# APM9328_CONNECTORL.net
KiCad netlist of a schematic drawn in Altium Designer
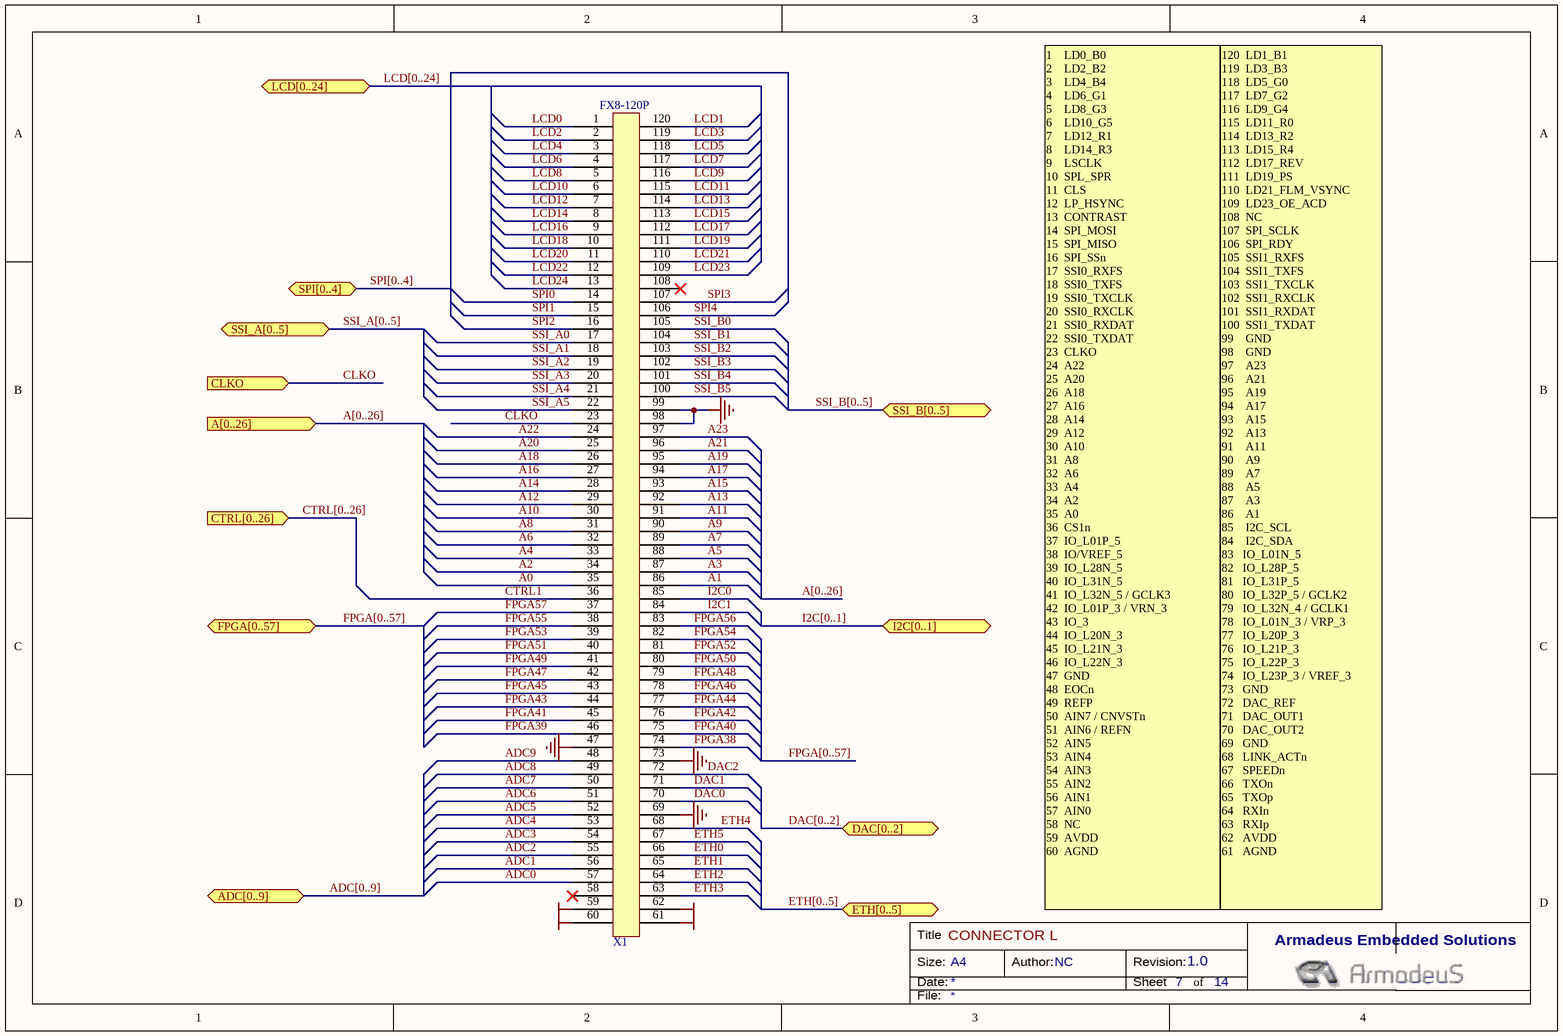
[diagram p0: APM9328_CONNECTORL.SchDoc]

(export (version "E")
  (design (tool "Eeschema 10.0.6"))
  (components
    (comp (ref "X1")
      (value "FX8-120P")
      (footprint "FX8-120P")
      (description "Fine Pitch Connector")
      (fields (field (name "MANUFACTURER") "Hirose") (field (name "PART NUMBER") "FX8-120P-SV"))
      (libsource (lib "*") (part "FX8-120P"))
    )
  )
  (nets
    (net (code "68") (name "/A0") (class "Default") (node (ref "X1") (pin "35") (pintype "passive")))
    (net (code "69") (name "/A1") (class "Default") (node (ref "X1") (pin "86") (pintype "passive")))
    (net (code "70") (name "/A2") (class "Default") (node (ref "X1") (pin "34") (pintype "passive")))
    (net (code "71") (name "/A3") (class "Default") (node (ref "X1") (pin "87") (pintype "passive")))
    (net (code "72") (name "/A4") (class "Default") (node (ref "X1") (pin "33") (pintype "passive")))
    (net (code "73") (name "/A5") (class "Default") (node (ref "X1") (pin "88") (pintype "passive")))
    (net (code "74") (name "/A6") (class "Default") (node (ref "X1") (pin "32") (pintype "passive")))
    (net (code "75") (name "/A7") (class "Default") (node (ref "X1") (pin "89") (pintype "passive")))
    (net (code "76") (name "/A8") (class "Default") (node (ref "X1") (pin "31") (pintype "passive")))
    (net (code "77") (name "/A9") (class "Default") (node (ref "X1") (pin "90") (pintype "passive")))
    (net (code "78") (name "/A10") (class "Default") (node (ref "X1") (pin "30") (pintype "passive")))
    (net (code "79") (name "/A11") (class "Default") (node (ref "X1") (pin "91") (pintype "passive")))
    (net (code "80") (name "/A12") (class "Default") (node (ref "X1") (pin "29") (pintype "passive")))
    (net (code "81") (name "/A13") (class "Default") (node (ref "X1") (pin "92") (pintype "passive")))
    (net (code "82") (name "/A14") (class "Default") (node (ref "X1") (pin "28") (pintype "passive")))
    (net (code "83") (name "/A15") (class "Default") (node (ref "X1") (pin "93") (pintype "passive")))
    (net (code "84") (name "/A16") (class "Default") (node (ref "X1") (pin "27") (pintype "passive")))
    (net (code "85") (name "/A17") (class "Default") (node (ref "X1") (pin "94") (pintype "passive")))
    (net (code "86") (name "/A18") (class "Default") (node (ref "X1") (pin "26") (pintype "passive")))
    (net (code "87") (name "/A19") (class "Default") (node (ref "X1") (pin "95") (pintype "passive")))
    (net (code "88") (name "/A20") (class "Default") (node (ref "X1") (pin "25") (pintype "passive")))
    (net (code "89") (name "/A21") (class "Default") (node (ref "X1") (pin "96") (pintype "passive")))
    (net (code "90") (name "/A22") (class "Default") (node (ref "X1") (pin "24") (pintype "passive")))
    (net (code "91") (name "/A23") (class "Default") (node (ref "X1") (pin "97") (pintype "passive")))
    (net (code "92") (name "/ADC0") (class "Default") (node (ref "X1") (pin "57") (pintype "passive")))
    (net (code "93") (name "/ADC1") (class "Default") (node (ref "X1") (pin "56") (pintype "passive")))
    (net (code "94") (name "/ADC2") (class "Default") (node (ref "X1") (pin "55") (pintype "passive")))
    (net (code "95") (name "/ADC3") (class "Default") (node (ref "X1") (pin "54") (pintype "passive")))
    (net (code "96") (name "/ADC4") (class "Default") (node (ref "X1") (pin "53") (pintype "passive")))
    (net (code "97") (name "/ADC5") (class "Default") (node (ref "X1") (pin "52") (pintype "passive")))
    (net (code "98") (name "/ADC6") (class "Default") (node (ref "X1") (pin "51") (pintype "passive")))
    (net (code "99") (name "/ADC7") (class "Default") (node (ref "X1") (pin "50") (pintype "passive")))
    (net (code "100") (name "/ADC8") (class "Default") (node (ref "X1") (pin "49") (pintype "passive")))
    (net (code "101") (name "/ADC9") (class "Default") (node (ref "X1") (pin "48") (pintype "passive")))
    (net (code "104") (name "/CLKO") (class "Default") (node (ref "X1") (pin "23") (pintype "passive")))
    (net (code "105") (name "/CTRL1") (class "Default") (node (ref "X1") (pin "36") (pintype "passive")))
    (net (code "107") (name "/DAC0") (class "Default") (node (ref "X1") (pin "70") (pintype "passive")))
    (net (code "108") (name "/DAC1") (class "Default") (node (ref "X1") (pin "71") (pintype "passive")))
    (net (code "109") (name "/DAC2") (class "Default") (node (ref "X1") (pin "72") (pintype "passive")))
    (net (code "111") (name "/ETH0") (class "Default") (node (ref "X1") (pin "66") (pintype "passive")))
    (net (code "112") (name "/ETH1") (class "Default") (node (ref "X1") (pin "65") (pintype "passive")))
    (net (code "113") (name "/ETH2") (class "Default") (node (ref "X1") (pin "64") (pintype "passive")))
    (net (code "114") (name "/ETH3") (class "Default") (node (ref "X1") (pin "63") (pintype "passive")))
    (net (code "115") (name "/ETH4") (class "Default") (node (ref "X1") (pin "68") (pintype "passive")))
    (net (code "116") (name "/ETH5") (class "Default") (node (ref "X1") (pin "67") (pintype "passive")))
    (net (code "118") (name "/FPGA38") (class "Default") (node (ref "X1") (pin "74") (pintype "passive")))
    (net (code "119") (name "/FPGA39") (class "Default") (node (ref "X1") (pin "46") (pintype "passive")))
    (net (code "120") (name "/FPGA40") (class "Default") (node (ref "X1") (pin "75") (pintype "passive")))
    (net (code "121") (name "/FPGA41") (class "Default") (node (ref "X1") (pin "45") (pintype "passive")))
    (net (code "122") (name "/FPGA42") (class "Default") (node (ref "X1") (pin "76") (pintype "passive")))
    (net (code "123") (name "/FPGA43") (class "Default") (node (ref "X1") (pin "44") (pintype "passive")))
    (net (code "124") (name "/FPGA44") (class "Default") (node (ref "X1") (pin "77") (pintype "passive")))
    (net (code "125") (name "/FPGA45") (class "Default") (node (ref "X1") (pin "43") (pintype "passive")))
    (net (code "126") (name "/FPGA46") (class "Default") (node (ref "X1") (pin "78") (pintype "passive")))
    (net (code "127") (name "/FPGA47") (class "Default") (node (ref "X1") (pin "42") (pintype "passive")))
    (net (code "128") (name "/FPGA48") (class "Default") (node (ref "X1") (pin "79") (pintype "passive")))
    (net (code "129") (name "/FPGA49") (class "Default") (node (ref "X1") (pin "41") (pintype "passive")))
    (net (code "130") (name "/FPGA50") (class "Default") (node (ref "X1") (pin "80") (pintype "passive")))
    (net (code "131") (name "/FPGA51") (class "Default") (node (ref "X1") (pin "40") (pintype "passive")))
    (net (code "132") (name "/FPGA52") (class "Default") (node (ref "X1") (pin "81") (pintype "passive")))
    (net (code "133") (name "/FPGA53") (class "Default") (node (ref "X1") (pin "39") (pintype "passive")))
    (net (code "134") (name "/FPGA54") (class "Default") (node (ref "X1") (pin "82") (pintype "passive")))
    (net (code "135") (name "/FPGA55") (class "Default") (node (ref "X1") (pin "38") (pintype "passive")))
    (net (code "136") (name "/FPGA56") (class "Default") (node (ref "X1") (pin "83") (pintype "passive")))
    (net (code "137") (name "/FPGA57") (class "Default") (node (ref "X1") (pin "37") (pintype "passive")))
    (net (code "139") (name "/I2C0") (class "Default") (node (ref "X1") (pin "85") (pintype "passive")))
    (net (code "140") (name "/I2C1") (class "Default") (node (ref "X1") (pin "84") (pintype "passive")))
    (net (code "142") (name "/LCD0") (class "Default") (node (ref "X1") (pin "1") (pintype "passive")))
    (net (code "143") (name "/LCD1") (class "Default") (node (ref "X1") (pin "120") (pintype "passive")))
    (net (code "144") (name "/LCD2") (class "Default") (node (ref "X1") (pin "2") (pintype "passive")))
    (net (code "145") (name "/LCD3") (class "Default") (node (ref "X1") (pin "119") (pintype "passive")))
    (net (code "146") (name "/LCD4") (class "Default") (node (ref "X1") (pin "3") (pintype "passive")))
    (net (code "147") (name "/LCD5") (class "Default") (node (ref "X1") (pin "118") (pintype "passive")))
    (net (code "148") (name "/LCD6") (class "Default") (node (ref "X1") (pin "4") (pintype "passive")))
    (net (code "149") (name "/LCD7") (class "Default") (node (ref "X1") (pin "117") (pintype "passive")))
    (net (code "150") (name "/LCD8") (class "Default") (node (ref "X1") (pin "5") (pintype "passive")))
    (net (code "151") (name "/LCD9") (class "Default") (node (ref "X1") (pin "116") (pintype "passive")))
    (net (code "152") (name "/LCD10") (class "Default") (node (ref "X1") (pin "6") (pintype "passive")))
    (net (code "153") (name "/LCD11") (class "Default") (node (ref "X1") (pin "115") (pintype "passive")))
    (net (code "154") (name "/LCD12") (class "Default") (node (ref "X1") (pin "7") (pintype "passive")))
    (net (code "155") (name "/LCD13") (class "Default") (node (ref "X1") (pin "114") (pintype "passive")))
    (net (code "156") (name "/LCD14") (class "Default") (node (ref "X1") (pin "8") (pintype "passive")))
    (net (code "157") (name "/LCD15") (class "Default") (node (ref "X1") (pin "113") (pintype "passive")))
    (net (code "158") (name "/LCD16") (class "Default") (node (ref "X1") (pin "9") (pintype "passive")))
    (net (code "159") (name "/LCD17") (class "Default") (node (ref "X1") (pin "112") (pintype "passive")))
    (net (code "160") (name "/LCD18") (class "Default") (node (ref "X1") (pin "10") (pintype "passive")))
    (net (code "161") (name "/LCD19") (class "Default") (node (ref "X1") (pin "111") (pintype "passive")))
    (net (code "162") (name "/LCD20") (class "Default") (node (ref "X1") (pin "11") (pintype "passive")))
    (net (code "163") (name "/LCD21") (class "Default") (node (ref "X1") (pin "110") (pintype "passive")))
    (net (code "164") (name "/LCD22") (class "Default") (node (ref "X1") (pin "12") (pintype "passive")))
    (net (code "165") (name "/LCD23") (class "Default") (node (ref "X1") (pin "109") (pintype "passive")))
    (net (code "166") (name "/LCD24") (class "Default") (node (ref "X1") (pin "13") (pintype "passive")))
    (net (code "168") (name "/SPI0") (class "Default") (node (ref "X1") (pin "14") (pintype "passive")))
    (net (code "169") (name "/SPI1") (class "Default") (node (ref "X1") (pin "15") (pintype "passive")))
    (net (code "170") (name "/SPI2") (class "Default") (node (ref "X1") (pin "16") (pintype "passive")))
    (net (code "171") (name "/SPI3") (class "Default") (node (ref "X1") (pin "107") (pintype "passive")))
    (net (code "172") (name "/SPI4") (class "Default") (node (ref "X1") (pin "106") (pintype "passive")))
    (net (code "174") (name "/SSI_A0") (class "Default") (node (ref "X1") (pin "17") (pintype "passive")))
    (net (code "175") (name "/SSI_A1") (class "Default") (node (ref "X1") (pin "18") (pintype "passive")))
    (net (code "176") (name "/SSI_A2") (class "Default") (node (ref "X1") (pin "19") (pintype "passive")))
    (net (code "177") (name "/SSI_A3") (class "Default") (node (ref "X1") (pin "20") (pintype "passive")))
    (net (code "178") (name "/SSI_A4") (class "Default") (node (ref "X1") (pin "21") (pintype "passive")))
    (net (code "179") (name "/SSI_A5") (class "Default") (node (ref "X1") (pin "22") (pintype "passive")))
    (net (code "181") (name "/SSI_B0") (class "Default") (node (ref "X1") (pin "105") (pintype "passive")))
    (net (code "182") (name "/SSI_B1") (class "Default") (node (ref "X1") (pin "104") (pintype "passive")))
    (net (code "183") (name "/SSI_B2") (class "Default") (node (ref "X1") (pin "103") (pintype "passive")))
    (net (code "184") (name "/SSI_B3") (class "Default") (node (ref "X1") (pin "102") (pintype "passive")))
    (net (code "185") (name "/SSI_B4") (class "Default") (node (ref "X1") (pin "101") (pintype "passive")))
    (net (code "186") (name "/SSI_B5") (class "Default") (node (ref "X1") (pin "100") (pintype "passive")))
    (net (code "188") (name "AGND") (class "Default")
      (node (ref "X1") (pin "60") (pintype "passive"))
      (node (ref "X1") (pin "61") (pintype "passive"))
    )
    (net (code "189") (name "AVDD") (class "Default")
      (node (ref "X1") (pin "59") (pintype "passive"))
      (node (ref "X1") (pin "62") (pintype "passive"))
    )
    (net (code "190") (name "GND") (class "Default")
      (node (ref "X1") (pin "47") (pintype "passive"))
      (node (ref "X1") (pin "69") (pintype "passive"))
      (node (ref "X1") (pin "73") (pintype "passive"))
      (node (ref "X1") (pin "98") (pintype "passive"))
      (node (ref "X1") (pin "99") (pintype "passive"))
    )
    (net (code "191") (name "unconnected-(X1-Pad58)") (class "Default")
      (node (ref "X1") (pin "58") (pintype "passive+no_connect"))
    )
    (net (code "192") (name "unconnected-(X1-Pad108)") (class "Default")
      (node (ref "X1") (pin "108") (pintype "passive+no_connect"))
    )
  )
)
